# untitled.net
KiCad netlist of a schematic drawn in EAGLE
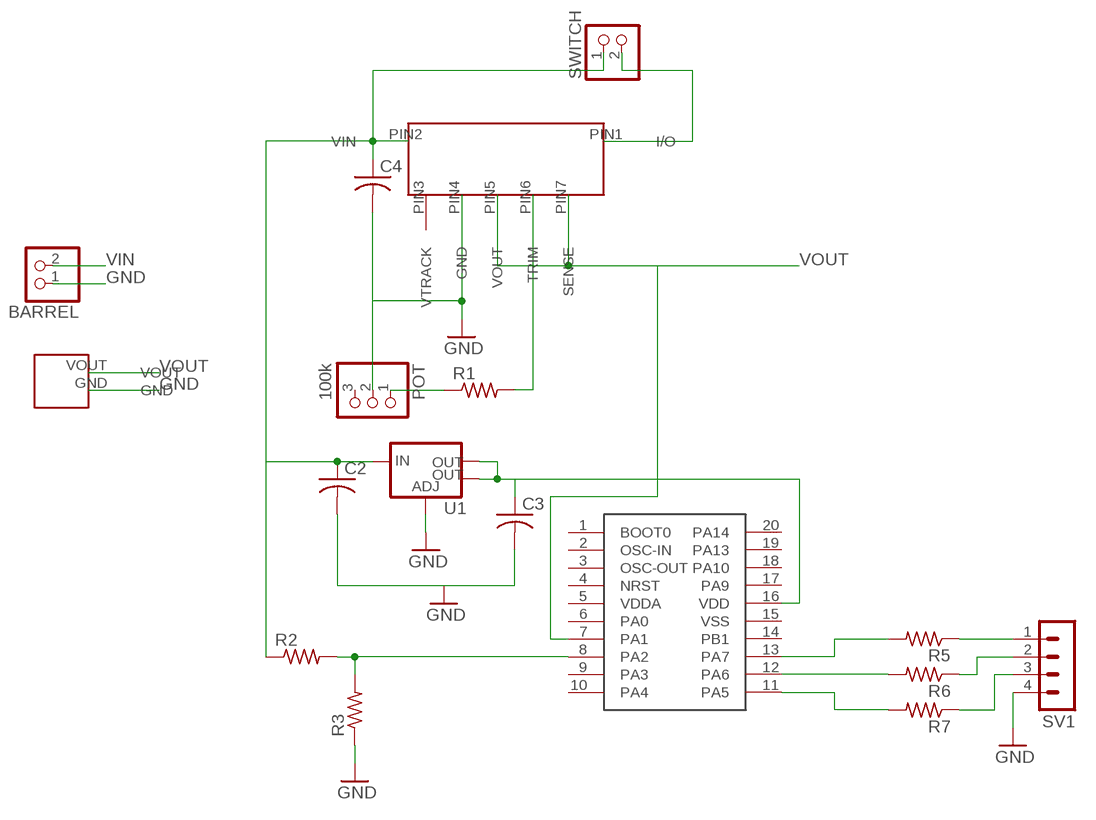
[diagram p0: schematic, sheet 1]

(export (version "E")
  (design (tool "Eeschema 10.0.6"))
  (components
    (comp (ref "BARREL")
      (value "PINHD-1X2")
      (footprint "eagle-import:1X02")
      (libsource (lib "eagle-import") (part "PINHD-1X2"))
    )
    (comp (ref "C2")
      (value "C-USC1206")
      (footprint "eagle-import:C1206")
      (libsource (lib "eagle-import") (part "C-USC1206"))
    )
    (comp (ref "C3")
      (value "C-USC1206")
      (footprint "eagle-import:C1206")
      (libsource (lib "eagle-import") (part "C-USC1206"))
    )
    (comp (ref "C4")
      (value "C-USC1206")
      (footprint "eagle-import:C1206")
      (libsource (lib "eagle-import") (part "C-USC1206"))
    )
    (comp (ref "OKY-T/16-D12N-C")
      (value "OKY-T/16-D12N-C")
      (footprint "eagle-import:OKY-T_16-D12N-C")
      (libsource (lib "eagle-import") (part "OKY-T/16-D12N-C"))
    )
    (comp (ref "POT")
      (value "100k")
      (footprint "eagle-import:1X03")
      (libsource (lib "eagle-import") (part "PINHD-1X3"))
    )
    (comp (ref "POWER")
      (value "POWER")
      (footprint "eagle-import:POWER")
      (libsource (lib "eagle-import") (part "POWER"))
    )
    (comp (ref "R1")
      (value "R-US_R1206")
      (footprint "eagle-import:R1206")
      (libsource (lib "eagle-import") (part "R-US_R1206"))
    )
    (comp (ref "R2")
      (value "R-US_R1206")
      (footprint "eagle-import:R1206")
      (libsource (lib "eagle-import") (part "R-US_R1206"))
    )
    (comp (ref "R3")
      (value "R-US_R1206")
      (footprint "eagle-import:R1206")
      (libsource (lib "eagle-import") (part "R-US_R1206"))
    )
    (comp (ref "R5")
      (value "R-US_R1206")
      (footprint "eagle-import:R1206")
      (libsource (lib "eagle-import") (part "R-US_R1206"))
    )
    (comp (ref "R6")
      (value "R-US_R1206")
      (footprint "eagle-import:R1206")
      (libsource (lib "eagle-import") (part "R-US_R1206"))
    )
    (comp (ref "R7")
      (value "R-US_R1206")
      (footprint "eagle-import:R1206")
      (libsource (lib "eagle-import") (part "R-US_R1206"))
    )
    (comp (ref "SV1")
      (value "MA04-1")
      (footprint "eagle-import:MA04-1")
      (libsource (lib "eagle-import") (part "MA04-1"))
    )
    (comp (ref "SWITCH")
      (value "PINHD-1X2")
      (footprint "eagle-import:1X02")
      (libsource (lib "eagle-import") (part "PINHD-1X2"))
    )
    (comp (ref "U$1")
      (value "STM32F07")
      (footprint "eagle-import:TSSOP20")
      (libsource (lib "eagle-import") (part "STM32F07"))
    )
    (comp (ref "U1")
      (value "V_REG_LM1117SOT223")
      (footprint "eagle-import:SOT223")
      (libsource (lib "eagle-import") (part "V_REG_LM1117SOT223"))
    )
  )
  (nets
    (net (code "1") (name "/VIN") (class "Default")
      (node (ref "BARREL") (pin "2") (pinfunction "2_2") (pintype "passive"))
      (node (ref "C2") (pin "1") (pinfunction "1_1") (pintype "passive"))
      (node (ref "C4") (pin "1") (pinfunction "1_1") (pintype "passive"))
      (node (ref "OKY-T/16-D12N-C") (pin "PIN2") (pinfunction "VIN_PIN2") (pintype "bidirectional"))
      (node (ref "R2") (pin "1") (pinfunction "1_1") (pintype "passive"))
      (node (ref "SWITCH") (pin "1") (pinfunction "1_1") (pintype "passive"))
      (node (ref "U1") (pin "3") (pinfunction "IN_3") (pintype "input"))
    )
    (net (code "2") (name "/VOUT") (class "Default")
      (node (ref "OKY-T/16-D12N-C") (pin "PIN5") (pinfunction "VOUT_PIN5") (pintype "bidirectional"))
      (node (ref "OKY-T/16-D12N-C") (pin "PIN7") (pinfunction "SENSE_PIN7") (pintype "bidirectional"))
      (node (ref "POWER") (pin "VOUT") (pinfunction "VOUT_VOUT") (pintype "bidirectional"))
      (node (ref "U$1") (pin "7") (pinfunction "PA1_7") (pintype "bidirectional"))
    )
    (net (code "3") (name "GND") (class "Default")
      (node (ref "BARREL") (pin "1") (pinfunction "1_1") (pintype "passive"))
      (node (ref "C2") (pin "2") (pinfunction "2_2") (pintype "passive"))
      (node (ref "C3") (pin "2") (pinfunction "2_2") (pintype "passive"))
      (node (ref "C4") (pin "2") (pinfunction "2_2") (pintype "passive"))
      (node (ref "OKY-T/16-D12N-C") (pin "PIN4") (pinfunction "GND_PIN4") (pintype "bidirectional"))
      (node (ref "POT") (pin "2") (pinfunction "2_2") (pintype "passive"))
      (node (ref "POWER") (pin "GND") (pinfunction "GND_GND") (pintype "bidirectional"))
      (node (ref "R3") (pin "1") (pinfunction "1_1") (pintype "passive"))
      (node (ref "SV1") (pin "4") (pinfunction "4_4") (pintype "passive"))
      (node (ref "U1") (pin "1") (pinfunction "ADJ_1") (pintype "input"))
    )
    (net (code "4") (name "Net-(OKY-T/16-D12N-C-I{slash}O)") (class "Default")
      (node (ref "OKY-T/16-D12N-C") (pin "PIN1") (pinfunction "I/O_PIN1") (pintype "bidirectional"))
      (node (ref "SWITCH") (pin "2") (pinfunction "2_2") (pintype "passive"))
    )
    (net (code "5") (name "Net-(OKY-T/16-D12N-C-TRIM)") (class "Default")
      (node (ref "OKY-T/16-D12N-C") (pin "PIN6") (pinfunction "TRIM_PIN6") (pintype "bidirectional"))
      (node (ref "R1") (pin "2") (pinfunction "2_2") (pintype "passive"))
    )
    (net (code "6") (name "Net-(POT-Pad1)") (class "Default")
      (node (ref "POT") (pin "1") (pinfunction "1_1") (pintype "passive"))
      (node (ref "R1") (pin "1") (pinfunction "1_1") (pintype "passive"))
    )
    (net (code "7") (name "Net-(R5-Pad1)") (class "Default")
      (node (ref "R5") (pin "1") (pinfunction "1_1") (pintype "passive"))
      (node (ref "SV1") (pin "1") (pinfunction "1_1") (pintype "passive"))
    )
    (net (code "8") (name "Net-(R6-Pad1)") (class "Default")
      (node (ref "R6") (pin "1") (pinfunction "1_1") (pintype "passive"))
      (node (ref "SV1") (pin "2") (pinfunction "2_2") (pintype "passive"))
    )
    (net (code "9") (name "Net-(R7-Pad1)") (class "Default")
      (node (ref "R7") (pin "1") (pinfunction "1_1") (pintype "passive"))
      (node (ref "SV1") (pin "3") (pinfunction "3_3") (pintype "passive"))
    )
    (net (code "10") (name "Net-(U$1-PA2)") (class "Default")
      (node (ref "R2") (pin "2") (pinfunction "2_2") (pintype "passive"))
      (node (ref "R3") (pin "2") (pinfunction "2_2") (pintype "passive"))
      (node (ref "U$1") (pin "8") (pinfunction "PA2_8") (pintype "bidirectional"))
    )
    (net (code "11") (name "Net-(U$1-PA5)") (class "Default")
      (node (ref "R7") (pin "2") (pinfunction "2_2") (pintype "passive"))
      (node (ref "U$1") (pin "11") (pinfunction "PA5_11") (pintype "bidirectional"))
    )
    (net (code "12") (name "Net-(U$1-PA6)") (class "Default")
      (node (ref "R6") (pin "2") (pinfunction "2_2") (pintype "passive"))
      (node (ref "U$1") (pin "12") (pinfunction "PA6_12") (pintype "bidirectional"))
    )
    (net (code "13") (name "Net-(U$1-PA7)") (class "Default")
      (node (ref "R5") (pin "2") (pinfunction "2_2") (pintype "passive"))
      (node (ref "U$1") (pin "13") (pinfunction "PA7_13") (pintype "bidirectional"))
    )
    (net (code "14") (name "Net-(U$1-VDD)") (class "Default")
      (node (ref "C3") (pin "1") (pinfunction "1_1") (pintype "passive"))
      (node (ref "U$1") (pin "16") (pinfunction "VDD_16") (pintype "bidirectional"))
      (node (ref "U1") (pin "2") (pinfunction "OUT_2") (pintype "output"))
      (node (ref "U1") (pin "4") (pinfunction "OUT_4") (pintype "output"))
    )
    (net (code "15") (name "unconnected-(OKY-T/16-D12N-C-VTRACK-PadPIN3)") (class "Default")
      (node (ref "OKY-T/16-D12N-C") (pin "PIN3") (pinfunction "VTRACK_PIN3") (pintype "bidirectional"))
    )
    (net (code "16") (name "unconnected-(POT-Pad3)") (class "Default")
      (node (ref "POT") (pin "3") (pinfunction "3_3") (pintype "passive"))
    )
    (net (code "17") (name "unconnected-(U$1-BOOT0-Pad1)") (class "Default")
      (node (ref "U$1") (pin "1") (pinfunction "BOOT0_1") (pintype "bidirectional"))
    )
    (net (code "18") (name "unconnected-(U$1-NRST-Pad4)") (class "Default")
      (node (ref "U$1") (pin "4") (pinfunction "NRST_4") (pintype "bidirectional"))
    )
    (net (code "19") (name "unconnected-(U$1-OSC-IN-Pad2)") (class "Default")
      (node (ref "U$1") (pin "2") (pinfunction "OSC-IN_2") (pintype "bidirectional"))
    )
    (net (code "20") (name "unconnected-(U$1-OSC-OUT-Pad3)") (class "Default")
      (node (ref "U$1") (pin "3") (pinfunction "OSC-OUT_3") (pintype "bidirectional"))
    )
    (net (code "21") (name "unconnected-(U$1-PA0-Pad6)") (class "Default")
      (node (ref "U$1") (pin "6") (pinfunction "PA0_6") (pintype "bidirectional"))
    )
    (net (code "22") (name "unconnected-(U$1-PA3-Pad9)") (class "Default")
      (node (ref "U$1") (pin "9") (pinfunction "PA3_9") (pintype "bidirectional"))
    )
    (net (code "23") (name "unconnected-(U$1-PA4-Pad10)") (class "Default")
      (node (ref "U$1") (pin "10") (pinfunction "PA4_10") (pintype "bidirectional"))
    )
    (net (code "24") (name "unconnected-(U$1-PA9-Pad17)") (class "Default")
      (node (ref "U$1") (pin "17") (pinfunction "PA9_17") (pintype "bidirectional"))
    )
    (net (code "25") (name "unconnected-(U$1-PA10-Pad18)") (class "Default")
      (node (ref "U$1") (pin "18") (pinfunction "PA10_18") (pintype "bidirectional"))
    )
    (net (code "26") (name "unconnected-(U$1-PA13-Pad19)") (class "Default")
      (node (ref "U$1") (pin "19") (pinfunction "PA13_19") (pintype "bidirectional"))
    )
    (net (code "27") (name "unconnected-(U$1-PA14-Pad20)") (class "Default")
      (node (ref "U$1") (pin "20") (pinfunction "PA14_20") (pintype "bidirectional"))
    )
    (net (code "28") (name "unconnected-(U$1-PB1-Pad14)") (class "Default")
      (node (ref "U$1") (pin "14") (pinfunction "PB1_14") (pintype "bidirectional"))
    )
    (net (code "29") (name "unconnected-(U$1-VDDA-Pad5)") (class "Default")
      (node (ref "U$1") (pin "5") (pinfunction "VDDA_5") (pintype "bidirectional"))
    )
    (net (code "30") (name "unconnected-(U$1-VSS-Pad15)") (class "Default")
      (node (ref "U$1") (pin "15") (pinfunction "VSS_15") (pintype "bidirectional"))
    )
  )
)
